# 15_2.net
KiCad netlist of a schematic drawn in EasyEDA Pro
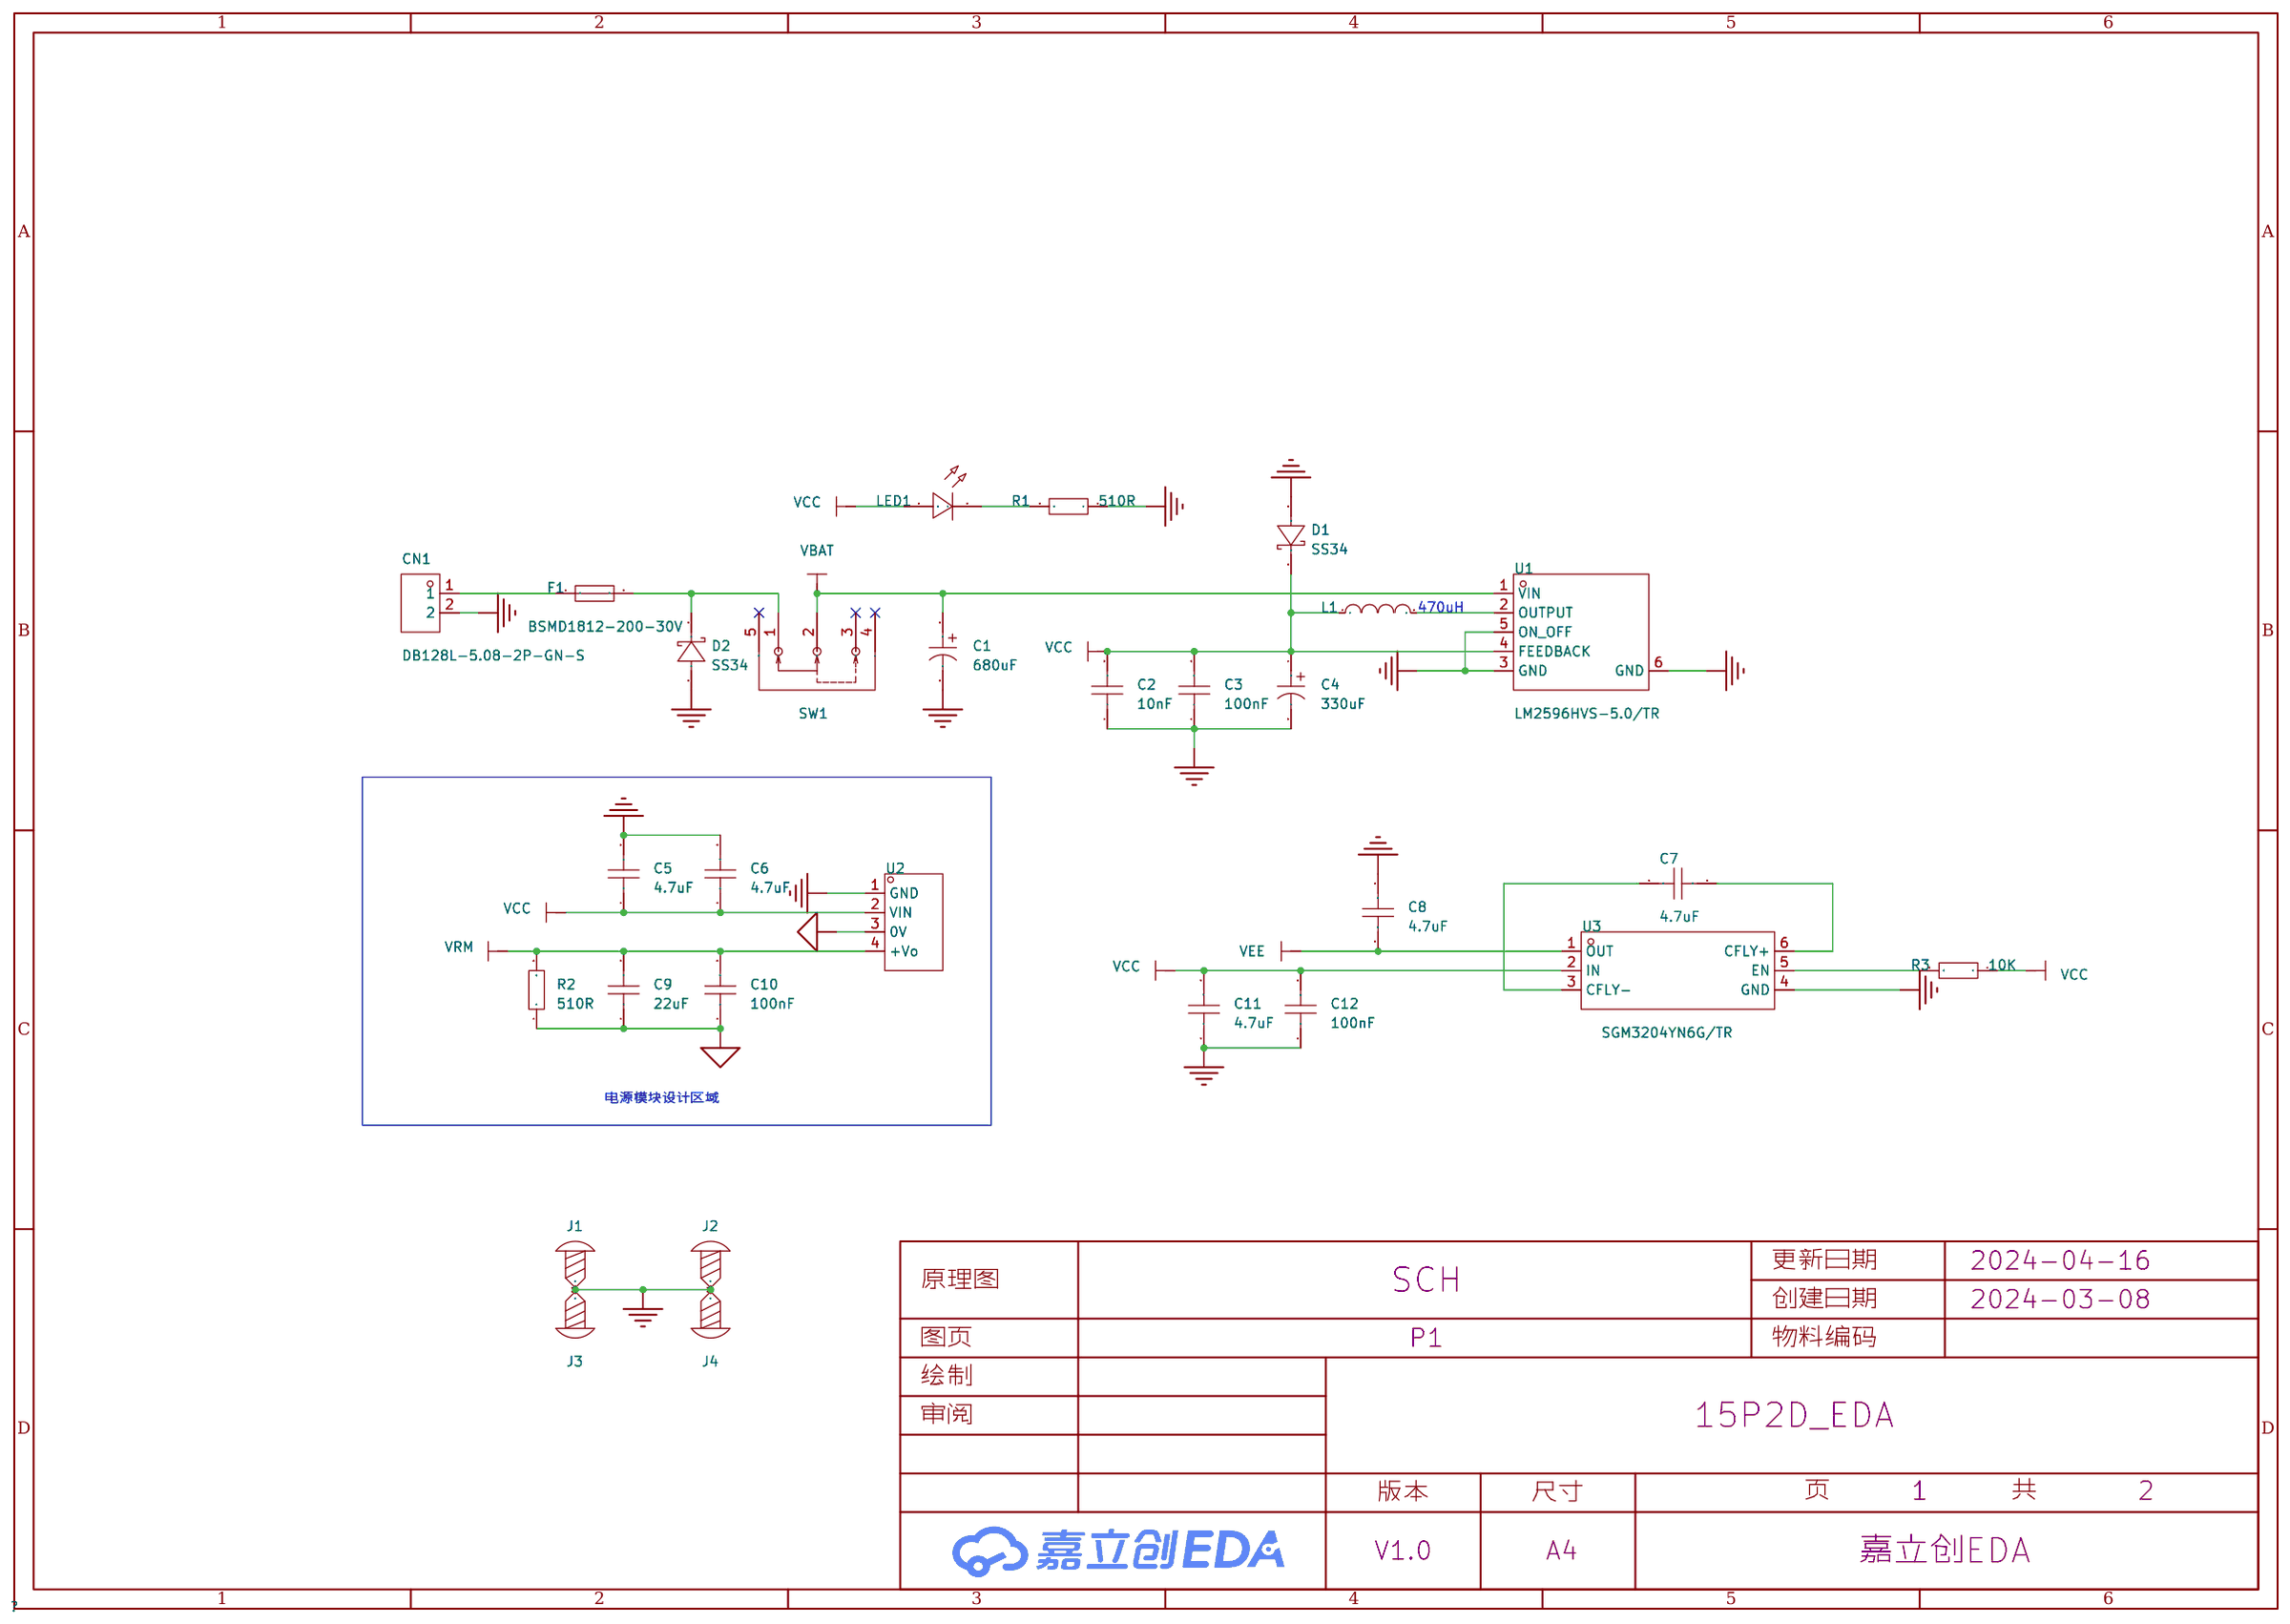
[diagram p0: P1]
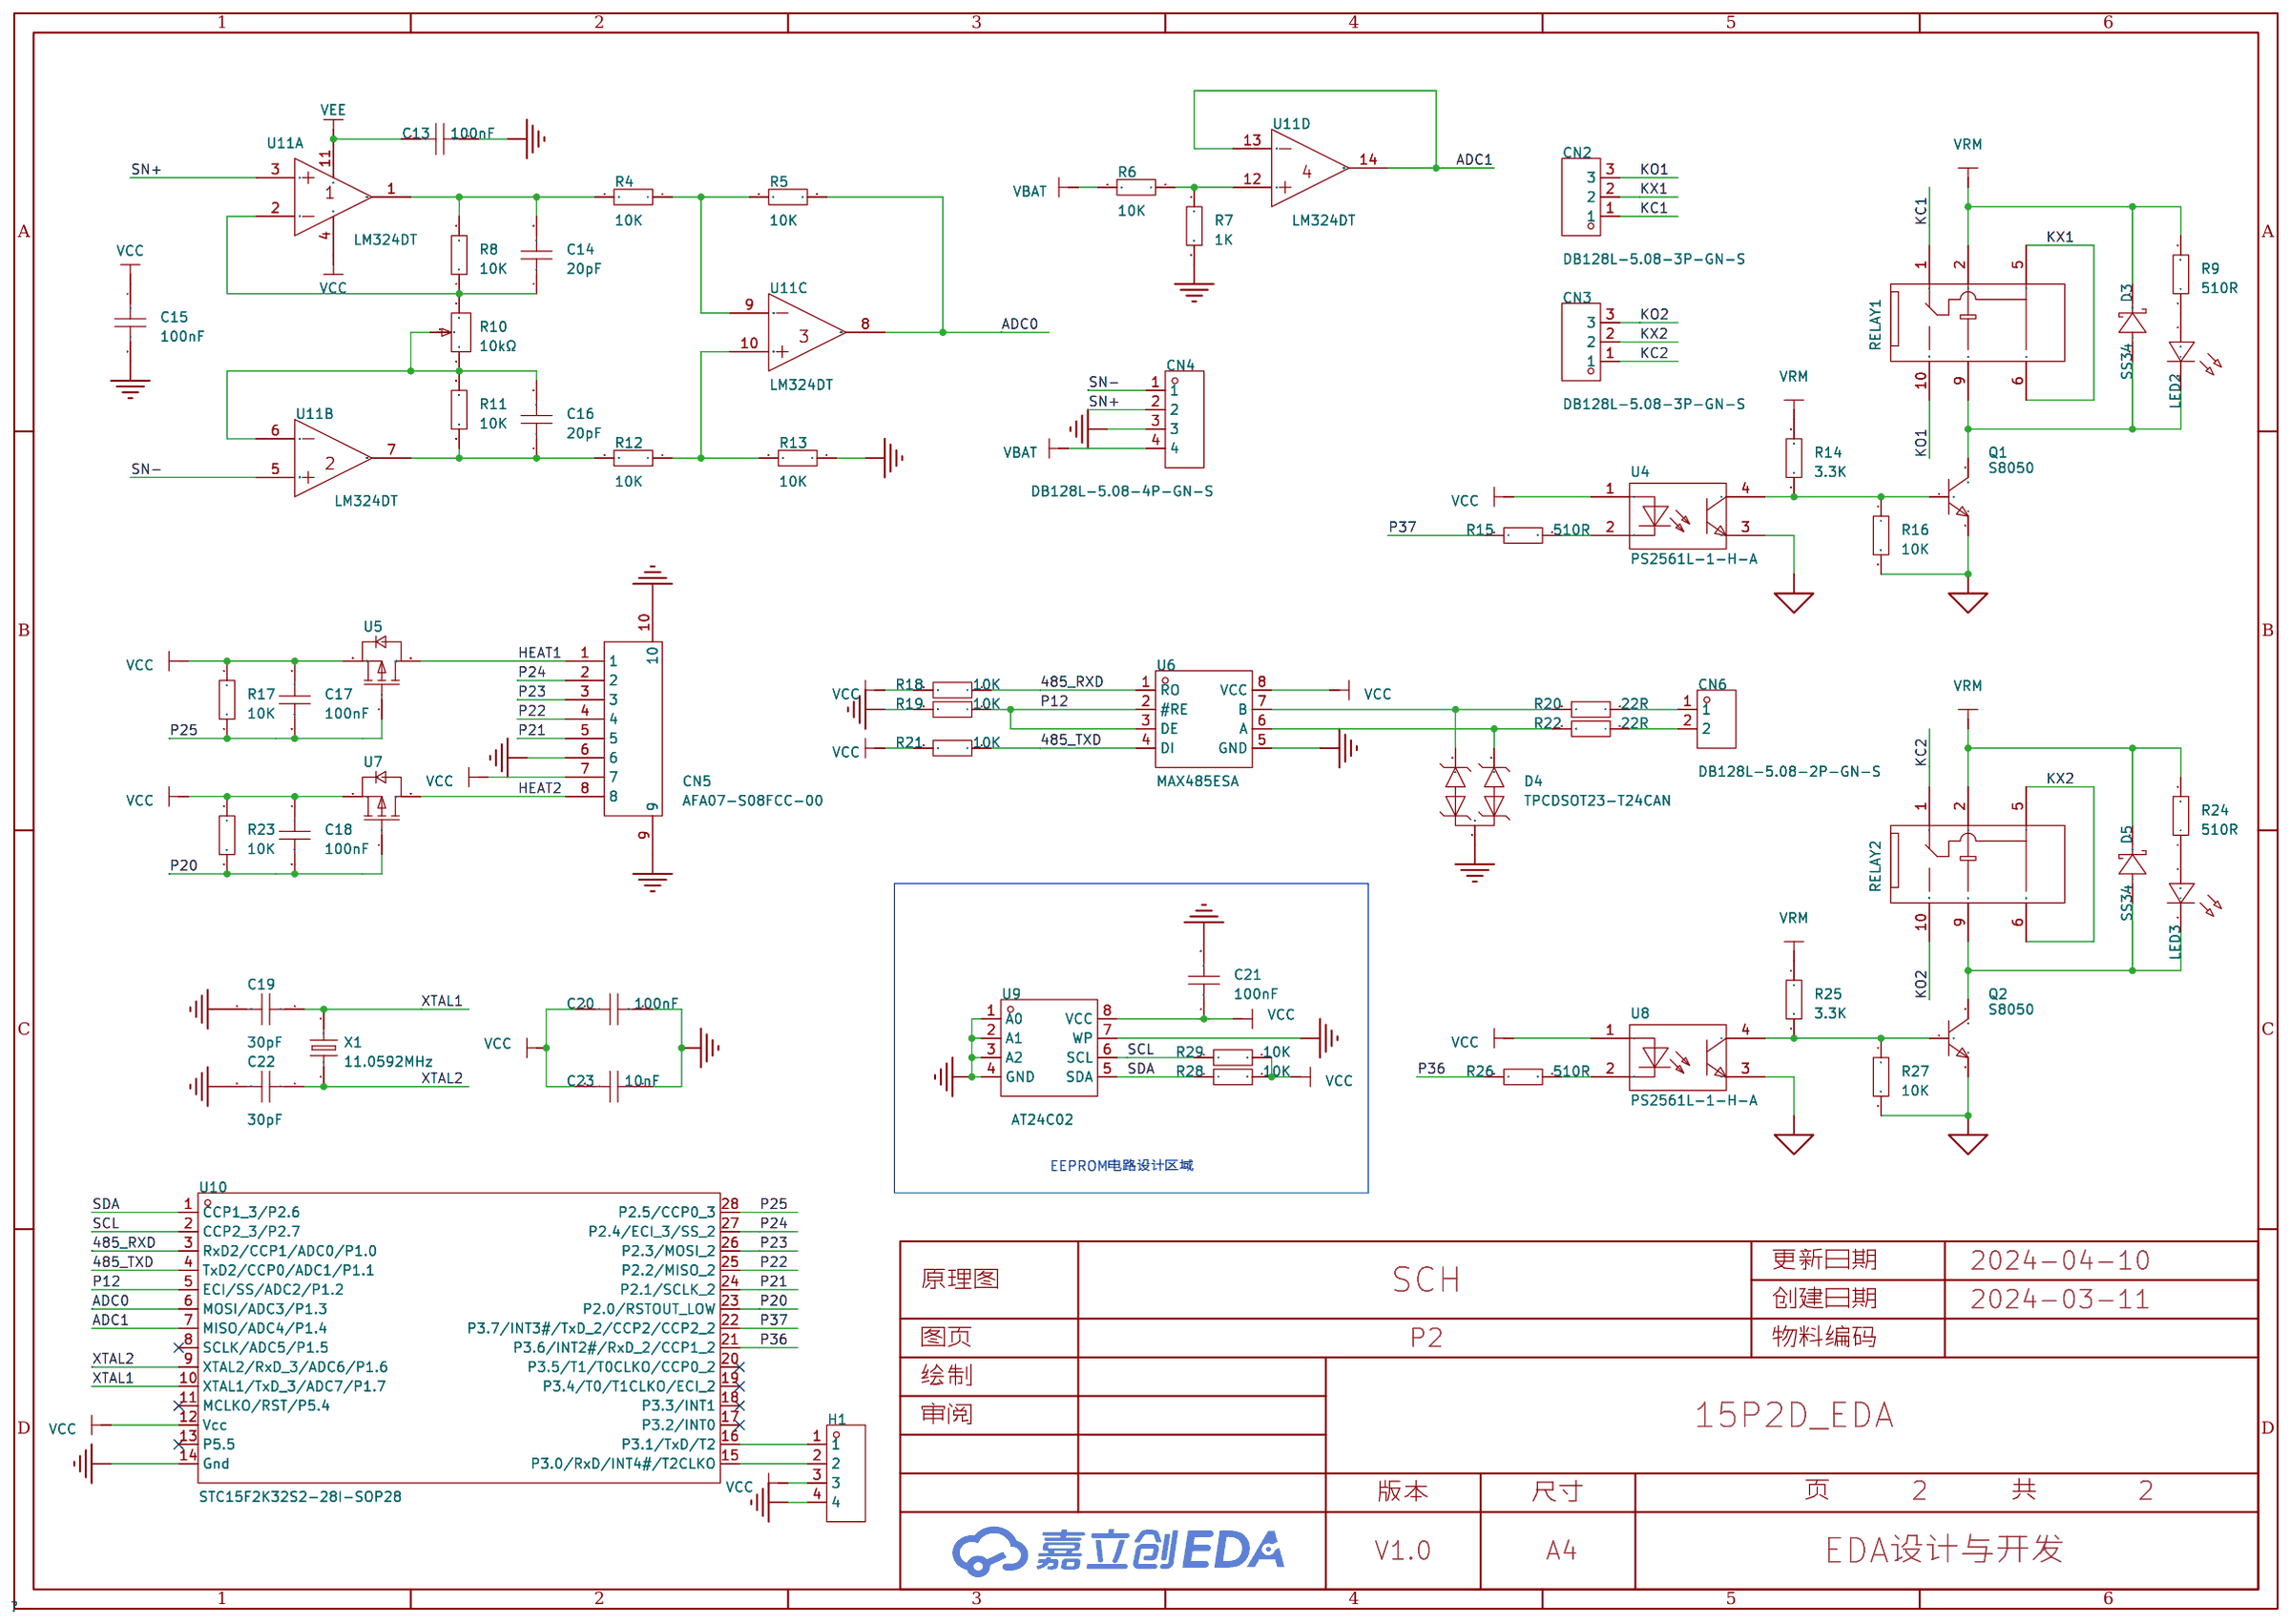
[diagram p1: P2]

(export (version "E")
  (design (tool "Eeschema 10.0.6"))
  (components
    (comp (ref "C1")
      (value "680uF")
      (footprint "easyedapro:CAP-SMD_BD10.0-L10.3-W10.3-LS11.3-FD")
      (description "容值:680uF;精度:±20%;额定电压:35V;纹波电流:380mA;")
      (fields (field (name "Manufacturer Part") "126RV0105") (field (name "Manufacturer") "KNSCHA(科尼盛)"))
      (libsource (lib "easyedapro") (part "126RV0105"))
    )
    (comp (ref "C2")
      (value "10nF")
      (footprint "easyedapro:C0805")
      (libsource (lib "easyedapro") (part "CapAcitance"))
    )
    (comp (ref "C3")
      (value "100nF")
      (footprint "easyedapro:C0805")
      (libsource (lib "easyedapro") (part "CapAcitance"))
    )
    (comp (ref "C4")
      (value "330uF")
      (footprint "easyedapro:CAP-SMD_BD6.3-L6.6-W6.6-LS7.6-RD")
      (description "容值:330uF;精度:±20%;额定电压:16V;纹波电流:170mA;")
      (fields (field (name "Manufacturer Part") "126RV0107") (field (name "Manufacturer") "KNSCHA(科尼盛)"))
      (libsource (lib "easyedapro") (part "126RV0107"))
    )
    (comp (ref "C5")
      (value "4.7uF")
      (footprint "easyedapro:C1206")
      (description "容值:22uF;精度:±10%;额定电压:16V;材质(温度系数):X5R;")
      (fields
        (field (name "Manufacturer Part") "CL31A226KOHNNNE")
        (field (name "Manufacturer") "SAMSUNG(三星)")
      )
      (libsource (lib "easyedapro") (part "CL31A226KOHNNNE"))
    )
    (comp (ref "C6")
      (value "4.7uF")
      (footprint "easyedapro:C1206")
      (description "容值:22uF;精度:±10%;额定电压:16V;材质(温度系数):X5R;")
      (fields
        (field (name "Manufacturer Part") "CL31A226KOHNNNE")
        (field (name "Manufacturer") "SAMSUNG(三星)")
      )
      (libsource (lib "easyedapro") (part "CL31A226KOHNNNE"))
    )
    (comp (ref "C7")
      (value "4.7uF")
      (footprint "easyedapro:C1206")
      (description "容值:22uF;精度:±10%;额定电压:16V;材质(温度系数):X5R;")
      (fields
        (field (name "Manufacturer Part") "CL31A226KOHNNNE")
        (field (name "Manufacturer") "SAMSUNG(三星)")
      )
      (libsource (lib "easyedapro") (part "CL31A226KOHNNNE"))
    )
    (comp (ref "C8")
      (value "4.7uF")
      (footprint "easyedapro:C1206")
      (description "容值:22uF;精度:±10%;额定电压:16V;材质(温度系数):X5R;")
      (fields
        (field (name "Manufacturer Part") "CL31A226KOHNNNE")
        (field (name "Manufacturer") "SAMSUNG(三星)")
      )
      (libsource (lib "easyedapro") (part "CL31A226KOHNNNE"))
    )
    (comp (ref "C9")
      (value "22uF")
      (footprint "easyedapro:C1206")
      (description "容值:22uF;精度:±10%;额定电压:16V;材质(温度系数):X5R;")
      (fields
        (field (name "Manufacturer Part") "CL31A226KOHNNNE")
        (field (name "Manufacturer") "SAMSUNG(三星)")
      )
      (libsource (lib "easyedapro") (part "CL31A226KOHNNNE"))
    )
    (comp (ref "C10")
      (value "100nF")
      (footprint "easyedapro:C0805")
      (libsource (lib "easyedapro") (part "CapAcitance"))
    )
    (comp (ref "C11")
      (value "4.7uF")
      (footprint "easyedapro:C1206")
      (description "容值:22uF;精度:±10%;额定电压:16V;材质(温度系数):X5R;")
      (fields
        (field (name "Manufacturer Part") "CL31A226KOHNNNE")
        (field (name "Manufacturer") "SAMSUNG(三星)")
      )
      (libsource (lib "easyedapro") (part "CL31A226KOHNNNE"))
    )
    (comp (ref "C12")
      (value "100nF")
      (footprint "easyedapro:C0805")
      (libsource (lib "easyedapro") (part "CapAcitance"))
    )
    (comp (ref "CN1")
      (value "DB128L-5.08-2P-GN-S")
      (footprint "easyedapro:CONN-TH_2P-P5.08_DB128L-5.08-2P")
      (fields (field (name "Manufacturer") "DORABO(地博电气)"))
      (libsource (lib "easyedapro") (part "DB128L-5.08-2P"))
    )
    (comp (ref "D1")
      (value "SS34")
      (footprint "easyedapro:SMA_L4.3-W2.5-LS5.0-RD")
      (description "二极管配置:独立式;正向压降(Vf):550mV@3A;直流反向耐压(Vr):40V;平均整流电流(Io):3A;")
      (fields (field (name "Manufacturer") "TWGMC(台湾迪嘉)"))
      (libsource (lib "easyedapro") (part "SS34_C727060"))
    )
    (comp (ref "D2")
      (value "SS34")
      (footprint "easyedapro:SMA_L4.3-W2.5-LS5.0-RD")
      (description "二极管配置:独立式;正向压降(Vf):550mV@3A;直流反向耐压(Vr):40V;平均整流电流(Io):3A;")
      (fields (field (name "Manufacturer") "TWGMC(台湾迪嘉)"))
      (libsource (lib "easyedapro") (part "SS34_C727060"))
    )
    (comp (ref "F1")
      (value "BSMD1812-200-30V")
      (footprint "easyedapro:F1812")
      (description "最大电压:30V;最大电流:40A;保持电流:2A;跳闸电流:4A;")
      (fields (field (name "Manufacturer") "BHFUSE(佰宏)"))
      (libsource (lib "easyedapro") (part "BSMD1812-200-30V"))
    )
    (comp (ref "J1") (value "~") (footprint "easyedapro:M2螺丝") (libsource (lib "easyedapro") (part "螺丝孔")))
    (comp (ref "J2") (value "~") (footprint "easyedapro:M2螺丝") (libsource (lib "easyedapro") (part "螺丝孔")))
    (comp (ref "J3") (value "~") (footprint "easyedapro:M2螺丝") (libsource (lib "easyedapro") (part "螺丝孔")))
    (comp (ref "J4") (value "~") (footprint "easyedapro:M2螺丝") (libsource (lib "easyedapro") (part "螺丝孔")))
    (comp (ref "L1")
      (value "470uH")
      (footprint "easyedapro:IND-SMD_L12.0-W12.0_YPRH120X")
      (description "电感值:470uH;精度:±20%;额定电流:1.06A;")
      (fields (field (name "Manufacturer Part") "YPRH1209-471M") (field (name "Manufacturer") "YJYCOIN(益嘉源)"))
      (libsource (lib "easyedapro") (part "YPRH1209-471M"))
    )
    (comp (ref "LED1")
      (value "~")
      (footprint "easyedapro:LED_TH-3mm")
      (libsource (lib "easyedapro") (part "LED_TH-R"))
    )
    (comp (ref "R1") (value "510R") (footprint "easyedapro:R0805") (libsource (lib "easyedapro") (part "电阻")))
    (comp (ref "R2") (value "510R") (footprint "easyedapro:R0805") (libsource (lib "easyedapro") (part "电阻")))
    (comp (ref "R3") (value "10K") (footprint "easyedapro:R0805") (libsource (lib "easyedapro") (part "电阻")))
    (comp (ref "SW1")
      (value "SK12D07VG4")
      (footprint "easyedapro:SW-TH_SK12D07VG4")
      (description "电路结构:单刀双掷;安装方式:侧插;额定电流(DC):500mA;额定电压(DC):50V;额定电流(AC):-;额定电压(AC):-;机械寿命:5千次;")
      (fields (field (name "Manufacturer") "SHOU HAN(首韩)"))
      (libsource (lib "easyedapro") (part "SK12D07VG4"))
    )
    (comp (ref "U1")
      (value "LM2596HVS-5.0/TR")
      (footprint "easyedapro:TO-263-5_L10.2-W8.9-P1.70-LS15.2-BR")
      (fields (field (name "Manufacturer") "HGSEMI(华冠)"))
      (libsource (lib "easyedapro") (part "LM2596HVS-5.0/TR"))
    )
    (comp (ref "U2") (value "~") (libsource (lib "easyedapro") (part "PCON")))
    (comp (ref "U3")
      (value "SGM3204YN6G/TR")
      (footprint "easyedapro:SOT-23-6_L2.9-W1.6-P0.95-LS2.8-BR")
      (description "功能类型:-;输入电压:1.4V~5.5V;输出电压:-5.5V~-1.4V;输出电流(最大值):200mA;")
      (fields (field (name "Manufacturer") "SGMICRO(圣邦微)"))
      (libsource (lib "easyedapro") (part "SGM3204YN6G/TR"))
    )
    (comp (ref "C13")
      (value "100nF")
      (footprint "easyedapro:C0805")
      (libsource (lib "easyedapro") (part "CapAcitance"))
    )
    (comp (ref "C14")
      (value "20pF")
      (footprint "easyedapro:C0805")
      (libsource (lib "easyedapro") (part "CapAcitance"))
    )
    (comp (ref "C15")
      (value "100nF")
      (footprint "easyedapro:C0805")
      (libsource (lib "easyedapro") (part "CapAcitance"))
    )
    (comp (ref "C16")
      (value "20pF")
      (footprint "easyedapro:C0805")
      (libsource (lib "easyedapro") (part "CapAcitance"))
    )
    (comp (ref "C17")
      (value "100nF")
      (footprint "easyedapro:C0805")
      (libsource (lib "easyedapro") (part "CapAcitance"))
    )
    (comp (ref "C18")
      (value "100nF")
      (footprint "easyedapro:C0805")
      (libsource (lib "easyedapro") (part "CapAcitance"))
    )
    (comp (ref "C19")
      (value "30pF")
      (footprint "easyedapro:C0805")
      (libsource (lib "easyedapro") (part "CapAcitance"))
    )
    (comp (ref "C20")
      (value "100nF")
      (footprint "easyedapro:C0805")
      (libsource (lib "easyedapro") (part "CapAcitance"))
    )
    (comp (ref "C21")
      (value "100nF")
      (footprint "easyedapro:C0805")
      (libsource (lib "easyedapro") (part "CapAcitance"))
    )
    (comp (ref "C22")
      (value "30pF")
      (footprint "easyedapro:C0805")
      (libsource (lib "easyedapro") (part "CapAcitance"))
    )
    (comp (ref "C23")
      (value "10nF")
      (footprint "easyedapro:C0805")
      (libsource (lib "easyedapro") (part "CapAcitance"))
    )
    (comp (ref "CN2")
      (value "DB128L-5.08-3P-GN-S")
      (footprint "easyedapro:CONN-TH_DB128L-5.08-3P")
      (fields (field (name "Manufacturer") "DORABO(地博电气)"))
      (libsource (lib "easyedapro") (part "DB128L-5.08-3P"))
    )
    (comp (ref "CN3")
      (value "DB128L-5.08-3P-GN-S")
      (footprint "easyedapro:CONN-TH_DB128L-5.08-3P")
      (fields (field (name "Manufacturer") "DORABO(地博电气)"))
      (libsource (lib "easyedapro") (part "DB128L-5.08-3P"))
    )
    (comp (ref "CN4")
      (value "DB128L-5.08-4P-GN-S")
      (footprint "easyedapro:CONN-TH_4P_DB128L-5.08-4P-GN-S")
      (fields (field (name "Manufacturer") "DORABO(地博电气)"))
      (libsource (lib "easyedapro") (part "DB128L-5.08-4P-GN-S"))
    )
    (comp (ref "CN5")
      (value "AFA07-S08FCC-00")
      (footprint "easyedapro:FPC-SMD_P1.00-8P_LCS-XJ-H2.5")
      (description "锁定特性:抽屉式;触点类型:下接;触点数量:8P;间距:1mm;安装类型:卧贴;")
      (fields (field (name "Manufacturer") "JS(钜硕电子)"))
      (libsource (lib "easyedapro") (part "AFA07-S08FCC-00"))
    )
    (comp (ref "CN6")
      (value "DB128L-5.08-2P-GN-S")
      (footprint "easyedapro:CONN-TH_2P-P5.08_DB128L-5.08-2P")
      (fields (field (name "Manufacturer") "DORABO(地博电气)"))
      (libsource (lib "easyedapro") (part "DB128L-5.08-2P"))
    )
    (comp (ref "D3")
      (value "SS34")
      (footprint "easyedapro:SMA_L4.3-W2.5-LS5.0-RD")
      (description "二极管配置:独立式;正向压降(Vf):550mV@3A;直流反向耐压(Vr):40V;平均整流电流(Io):3A;")
      (fields (field (name "Manufacturer") "TWGMC(台湾迪嘉)"))
      (libsource (lib "easyedapro") (part "SS34_C727060"))
    )
    (comp (ref "D4")
      (value "TPCDSOT23-T24CAN")
      (footprint "easyedapro:SOT-23-3_L2.9-W1.3-P1.90-LS2.4-BR")
      (fields (field (name "Manufacturer") "TECH PUBLIC(台舟)"))
      (libsource (lib "easyedapro") (part "TPCDSOT23-T24CAN"))
    )
    (comp (ref "D5")
      (value "SS34")
      (footprint "easyedapro:SMA_L4.3-W2.5-LS5.0-RD")
      (description "二极管配置:独立式;正向压降(Vf):550mV@3A;直流反向耐压(Vr):40V;平均整流电流(Io):3A;")
      (fields (field (name "Manufacturer") "TWGMC(台湾迪嘉)"))
      (libsource (lib "easyedapro") (part "SS34_C727060"))
    )
    (comp (ref "H1")
      (value "~")
      (footprint "easyedapro:HDR-TH_4P-P2.54-V-F")
      (libsource (lib "easyedapro") (part "2.54-1*4P母"))
    )
    (comp (ref "LED2")
      (value "~")
      (footprint "easyedapro:LED_TH-3mm")
      (libsource (lib "easyedapro") (part "LED_TH-G"))
    )
    (comp (ref "LED3")
      (value "~")
      (footprint "easyedapro:LED_TH-3mm")
      (libsource (lib "easyedapro") (part "LED_TH-G"))
    )
    (comp (ref "Q1")
      (value "S8050")
      (footprint "easyedapro:SOT-23-3_L2.9-W1.3-P1.90-LS2.4-BR")
      (description "晶体管类型:NPN;集电极电流(Ic):500mA;集射极击穿电压(Vceo):25V;功率(Pd):300mW;")
      (fields (field (name "Manufacturer") "YONGYUTAI(永裕泰)"))
      (libsource (lib "easyedapro") (part "S8050_C2891804"))
    )
    (comp (ref "Q2")
      (value "S8050")
      (footprint "easyedapro:SOT-23-3_L2.9-W1.3-P1.90-LS2.4-BR")
      (description "晶体管类型:NPN;集电极电流(Ic):500mA;集射极击穿电压(Vceo):25V;功率(Pd):300mW;")
      (fields (field (name "Manufacturer") "YONGYUTAI(永裕泰)"))
      (libsource (lib "easyedapro") (part "S8050_C2891804"))
    )
    (comp (ref "R4") (value "10K") (footprint "easyedapro:R0805") (libsource (lib "easyedapro") (part "电阻")))
    (comp (ref "R5") (value "10K") (footprint "easyedapro:R0805") (libsource (lib "easyedapro") (part "电阻")))
    (comp (ref "R6") (value "10K") (footprint "easyedapro:R0805") (libsource (lib "easyedapro") (part "电阻")))
    (comp (ref "R7") (value "1K") (footprint "easyedapro:R0805") (libsource (lib "easyedapro") (part "电阻")))
    (comp (ref "R8") (value "10K") (footprint "easyedapro:R0805") (libsource (lib "easyedapro") (part "电阻")))
    (comp (ref "R9") (value "510R") (footprint "easyedapro:R0805") (libsource (lib "easyedapro") (part "电阻")))
    (comp (ref "R10")
      (value "10kΩ")
      (footprint "easyedapro:RES-ADJ-TH_3P-L10.0-W10.0-P2.50-BL-BS")
      (description "阻值:20kΩ;精度:±10%;功率:500mW;温度系数:±100ppm/°C;")
      (fields (field (name "Manufacturer Part") "3296W-1-203LF") (field (name "Manufacturer") "BOURNS"))
      (libsource (lib "easyedapro") (part "3296W-1-203LF"))
    )
    (comp (ref "R11") (value "10K") (footprint "easyedapro:R0805") (libsource (lib "easyedapro") (part "电阻")))
    (comp (ref "R12") (value "10K") (footprint "easyedapro:R0805") (libsource (lib "easyedapro") (part "电阻")))
    (comp (ref "R13") (value "10K") (footprint "easyedapro:R0805") (libsource (lib "easyedapro") (part "电阻")))
    (comp (ref "R14")
      (value "3.3K")
      (footprint "easyedapro:R0805")
      (libsource (lib "easyedapro") (part "电阻"))
    )
    (comp (ref "R15")
      (value "510R")
      (footprint "easyedapro:R0805")
      (libsource (lib "easyedapro") (part "电阻"))
    )
    (comp (ref "R16") (value "10K") (footprint "easyedapro:R0805") (libsource (lib "easyedapro") (part "电阻")))
    (comp (ref "R17") (value "10K") (footprint "easyedapro:R0805") (libsource (lib "easyedapro") (part "电阻")))
    (comp (ref "R18") (value "10K") (footprint "easyedapro:R0805") (libsource (lib "easyedapro") (part "电阻")))
    (comp (ref "R19") (value "10K") (footprint "easyedapro:R0805") (libsource (lib "easyedapro") (part "电阻")))
    (comp (ref "R20") (value "22R") (footprint "easyedapro:R0805") (libsource (lib "easyedapro") (part "电阻")))
    (comp (ref "R21") (value "10K") (footprint "easyedapro:R0805") (libsource (lib "easyedapro") (part "电阻")))
    (comp (ref "R22") (value "22R") (footprint "easyedapro:R0805") (libsource (lib "easyedapro") (part "电阻")))
    (comp (ref "R23") (value "10K") (footprint "easyedapro:R0805") (libsource (lib "easyedapro") (part "电阻")))
    (comp (ref "R24")
      (value "510R")
      (footprint "easyedapro:R0805")
      (libsource (lib "easyedapro") (part "电阻"))
    )
    (comp (ref "R25")
      (value "3.3K")
      (footprint "easyedapro:R0805")
      (libsource (lib "easyedapro") (part "电阻"))
    )
    (comp (ref "R26")
      (value "510R")
      (footprint "easyedapro:R0805")
      (libsource (lib "easyedapro") (part "电阻"))
    )
    (comp (ref "R27") (value "10K") (footprint "easyedapro:R0805") (libsource (lib "easyedapro") (part "电阻")))
    (comp (ref "R28") (value "10K") (footprint "easyedapro:R0805") (libsource (lib "easyedapro") (part "电阻")))
    (comp (ref "R29") (value "10K") (footprint "easyedapro:R0805") (libsource (lib "easyedapro") (part "电阻")))
    (comp (ref "RELAY1")
      (value "G5V-1 DC5")
      (footprint "easyedapro:RELAY-TH_G5V-1")
      (description "线圈电压:5V;触点形式:一组转换:1C(单刀双掷-转换);触点容量(电阻负载):-;最大切换电压:125V@AC；60V@DC;最大切换电流:1A;")
      (fields (field (name "Manufacturer") "OMRON(欧姆龙)"))
      (libsource (lib "easyedapro") (part "G5V-1-5VDC"))
    )
    (comp (ref "RELAY2")
      (value "G5V-1 DC5")
      (footprint "easyedapro:RELAY-TH_G5V-1")
      (description "线圈电压:5V;触点形式:一组转换:1C(单刀双掷-转换);触点容量(电阻负载):-;最大切换电压:125V@AC；60V@DC;最大切换电流:1A;")
      (fields (field (name "Manufacturer") "OMRON(欧姆龙)"))
      (libsource (lib "easyedapro") (part "G5V-1-5VDC"))
    )
    (comp (ref "U4")
      (value "PS2561L-1-H-A")
      (footprint "easyedapro:SOP-4_L6.5-W4.6-P2.54-LS9.6-TL")
      (fields (field (name "Manufacturer") "California Eastern Laboratories"))
      (libsource (lib "easyedapro") (part "PS2561L-1-H-A"))
    )
    (comp (ref "U5")
      (value "SI2301-ZE")
      (footprint "easyedapro:SOT-23-3_L2.9-W1.3-P1.90-LS2.4-BR")
      (fields (field (name "Manufacturer") "HXY MOSFET(华轩阳电子)"))
      (libsource (lib "easyedapro") (part "SI2301-ZE"))
    )
    (comp (ref "U6")
      (value "MAX485ESA")
      (footprint "easyedapro:SOP-8_L5.0-W4.0-P1.27-LS6.0-BL")
      (fields (field (name "Manufacturer") "UMW(友台半导体)"))
      (libsource (lib "easyedapro") (part "MAX485EAS"))
    )
    (comp (ref "U7")
      (value "SI2301-ZE")
      (footprint "easyedapro:SOT-23-3_L2.9-W1.3-P1.90-LS2.4-BR")
      (fields (field (name "Manufacturer") "HXY MOSFET(华轩阳电子)"))
      (libsource (lib "easyedapro") (part "SI2301-ZE"))
    )
    (comp (ref "U8")
      (value "PS2561L-1-H-A")
      (footprint "easyedapro:SOP-4_L6.5-W4.6-P2.54-LS9.6-TL")
      (fields (field (name "Manufacturer") "California Eastern Laboratories"))
      (libsource (lib "easyedapro") (part "PS2561L-1-H-A"))
    )
    (comp (ref "U9")
      (value "AT24C02")
      (footprint "easyedapro:SOP-8_L4.9-W3.9-P1.27-LS6.0-BL")
      (description "接口类型:I2C;存储容量:2Kbit;时钟频率(fc):400kHz~1MHz;")
      (fields (field (name "Manufacturer") "HXY MOSFET(华轩阳电子)"))
      (libsource (lib "easyedapro") (part "AT24C02_C7470930"))
    )
    (comp (ref "U10")
      (value "STC15F2K32S2-28I-SOP28")
      (footprint "easyedapro:SOP-28_L17.9-W7.5-P1.27-LS10.3-BL")
      (fields (field (name "Manufacturer") "STC(宏晶)"))
      (libsource (lib "easyedapro") (part "STC15F2K32S2-28I-SOP28"))
    )
    (comp (ref "U11")
      (value "LM324DT")
      (footprint "easyedapro:SOIC-14_L8.7-W3.9-P1.27-LS6.0-BL")
      (description "放大器数:四路;增益带宽积(GBP):1.3MHz;输入偏置电流(Ib):20nA;压摆率(SR):0.4V/us;带宽(-3db):-;")
      (fields (field (name "Manufacturer") "ST(意法半导体)"))
      (libsource (lib "easyedapro") (part "LM324DT"))
    )
    (comp (ref "X1")
      (value "11.0592MHz")
      (footprint "easyedapro:HC-49US_L11.5-W4.5-P4.88")
      (description "晶振类型:直插晶振;频率:11.0592MHz;常温频差:±30ppm;外接负载电容:20pF;频率稳定度(全温):±30ppm;")
      (fields
        (field (name "Manufacturer Part") "TAXD11.0592M2GLFBET2T")
        (field (name "Manufacturer") "YJX(雅晶鑫)")
      )
      (libsource (lib "easyedapro") (part "HC-49S11.0592MHZ20PF30PPM"))
    )
  )
  (nets
    (net (code "1") (name "0") (class "Default")
      (node (ref "C10") (pin "1") (pinfunction "1_1") (pintype "input"))
      (node (ref "C9") (pin "1") (pinfunction "1_1") (pintype "unspecified"))
      (node (ref "Q1") (pin "2") (pinfunction "E_2") (pintype "unspecified"))
      (node (ref "Q2") (pin "2") (pinfunction "E_2") (pintype "unspecified"))
      (node (ref "R16") (pin "2") (pinfunction "2_2") (pintype "input"))
      (node (ref "R2") (pin "1") (pinfunction "1_1") (pintype "input"))
      (node (ref "R27") (pin "2") (pinfunction "2_2") (pintype "input"))
      (node (ref "U2") (pin "3") (pinfunction "0V_3") (pintype "input"))
      (node (ref "U4") (pin "3") (pinfunction "3_3") (pintype "input"))
      (node (ref "U8") (pin "3") (pinfunction "3_3") (pintype "input"))
    )
    (net (code "2") (name "485_RXD") (class "Default")
      (node (ref "R18") (pin "1") (pinfunction "1_1") (pintype "input"))
      (node (ref "U10") (pin "3") (pinfunction "RxD2/CCP1/ADC0/P1.0_3") (pintype "input"))
      (node (ref "U6") (pin "1") (pinfunction "RO_1") (pintype "unspecified"))
    )
    (net (code "3") (name "485_TXD") (class "Default")
      (node (ref "R21") (pin "1") (pinfunction "1_1") (pintype "input"))
      (node (ref "U10") (pin "4") (pinfunction "TxD2/CCP0/ADC1/P1.1_4") (pintype "input"))
      (node (ref "U6") (pin "4") (pinfunction "DI_4") (pintype "unspecified"))
    )
    (net (code "4") (name "ADC0") (class "Default")
      (node (ref "R5") (pin "1") (pinfunction "1_1") (pintype "input"))
      (node (ref "U10") (pin "6") (pinfunction "MOSI/ADC3/P1.3_6") (pintype "input"))
      (node (ref "U11") (pin "8") (pinfunction "OUT3_8") (pintype "unspecified"))
    )
    (net (code "5") (name "ADC1") (class "Default")
      (node (ref "U10") (pin "7") (pinfunction "MISO/ADC4/P1.4_7") (pintype "input"))
      (node (ref "U11") (pin "13") (pinfunction "IN4-_13") (pintype "unspecified"))
      (node (ref "U11") (pin "14") (pinfunction "OUT4_14") (pintype "unspecified"))
    )
    (net (code "6") (name "GND") (class "Default")
      (node (ref "C1") (pin "2") (pinfunction "2_2") (pintype "input"))
      (node (ref "C11") (pin "1") (pinfunction "1_1") (pintype "unspecified"))
      (node (ref "C12") (pin "1") (pinfunction "1_1") (pintype "input"))
      (node (ref "C13") (pin "1") (pinfunction "1_1") (pintype "input"))
      (node (ref "C15") (pin "2") (pinfunction "2_2") (pintype "input"))
      (node (ref "C19") (pin "2") (pinfunction "2_2") (pintype "input"))
      (node (ref "C2") (pin "1") (pinfunction "1_1") (pintype "input"))
      (node (ref "C20") (pin "1") (pinfunction "1_1") (pintype "input"))
      (node (ref "C21") (pin "2") (pinfunction "2_2") (pintype "input"))
      (node (ref "C22") (pin "2") (pinfunction "2_2") (pintype "input"))
      (node (ref "C23") (pin "1") (pinfunction "1_1") (pintype "input"))
      (node (ref "C3") (pin "1") (pinfunction "1_1") (pintype "input"))
      (node (ref "C4") (pin "2") (pinfunction "2_2") (pintype "input"))
      (node (ref "C5") (pin "2") (pinfunction "2_2") (pintype "unspecified"))
      (node (ref "C6") (pin "2") (pinfunction "2_2") (pintype "unspecified"))
      (node (ref "C8") (pin "1") (pinfunction "1_1") (pintype "unspecified"))
      (node (ref "CN1") (pin "2") (pinfunction "2_2") (pintype "unspecified"))
      (node (ref "CN4") (pin "3") (pinfunction "3_3") (pintype "unspecified"))
      (node (ref "CN5") (pin "10") (pinfunction "10_10") (pintype "unspecified"))
      (node (ref "CN5") (pin "6") (pinfunction "6_6") (pintype "unspecified"))
      (node (ref "CN5") (pin "9") (pinfunction "9_9") (pintype "unspecified"))
      (node (ref "D1") (pin "2") (pinfunction "A_2") (pintype "unspecified"))
      (node (ref "D2") (pin "2") (pinfunction "A_2") (pintype "unspecified"))
      (node (ref "D4") (pin "3") (pinfunction "3_3") (pintype "unspecified"))
      (node (ref "H1") (pin "4") (pinfunction "4_4") (pintype "unspecified"))
      (node (ref "J1") (pin "1") (pinfunction "1_1") (pintype "input"))
      (node (ref "J2") (pin "1") (pinfunction "1_1") (pintype "input"))
      (node (ref "J3") (pin "1") (pinfunction "1_1") (pintype "input"))
      (node (ref "J4") (pin "1") (pinfunction "1_1") (pintype "input"))
      (node (ref "R1") (pin "1") (pinfunction "1_1") (pintype "input"))
      (node (ref "R13") (pin "1") (pinfunction "1_1") (pintype "input"))
      (node (ref "R19") (pin "2") (pinfunction "2_2") (pintype "input"))
      (node (ref "R7") (pin "2") (pinfunction "2_2") (pintype "input"))
      (node (ref "U1") (pin "3") (pinfunction "GND_3") (pintype "input"))
      (node (ref "U1") (pin "5") (pinfunction "ON_OFF_5") (pintype "input"))
      (node (ref "U1") (pin "6") (pinfunction "GND_6") (pintype "input"))
      (node (ref "U10") (pin "14") (pinfunction "Gnd_14") (pintype "input"))
      (node (ref "U2") (pin "1") (pinfunction "GND_1") (pintype "input"))
      (node (ref "U3") (pin "4") (pinfunction "GND_4") (pintype "unspecified"))
      (node (ref "U6") (pin "5") (pinfunction "GND_5") (pintype "unspecified"))
      (node (ref "U9") (pin "1") (pinfunction "A0_1") (pintype "unspecified"))
      (node (ref "U9") (pin "2") (pinfunction "A1_2") (pintype "unspecified"))
      (node (ref "U9") (pin "3") (pinfunction "A2_3") (pintype "unspecified"))
      (node (ref "U9") (pin "4") (pinfunction "GND_4") (pintype "unspecified"))
      (node (ref "U9") (pin "7") (pinfunction "WP_7") (pintype "unspecified"))
    )
    (net (code "7") (name "HEAT1") (class "Default")
      (node (ref "CN5") (pin "1") (pinfunction "1_1") (pintype "unspecified"))
      (node (ref "U5") (pin "3") (pinfunction "D_3") (pintype "unspecified"))
    )
    (net (code "8") (name "HEAT2") (class "Default")
      (node (ref "CN5") (pin "8") (pinfunction "8_8") (pintype "unspecified"))
      (node (ref "U7") (pin "3") (pinfunction "D_3") (pintype "unspecified"))
    )
    (net (code "9") (name "KC1") (class "Default")
      (node (ref "CN2") (pin "1") (pinfunction "1_1") (pintype "unspecified"))
      (node (ref "RELAY1") (pin "1") (pinfunction "1_1") (pintype "input"))
    )
    (net (code "10") (name "KC2") (class "Default")
      (node (ref "CN3") (pin "1") (pinfunction "1_1") (pintype "unspecified"))
      (node (ref "RELAY2") (pin "1") (pinfunction "1_1") (pintype "input"))
    )
    (net (code "11") (name "KO1") (class "Default")
      (node (ref "CN2") (pin "3") (pinfunction "3_3") (pintype "unspecified"))
      (node (ref "RELAY1") (pin "10") (pinfunction "10_10") (pintype "input"))
    )
    (net (code "12") (name "KO2") (class "Default")
      (node (ref "CN3") (pin "3") (pinfunction "3_3") (pintype "unspecified"))
      (node (ref "RELAY2") (pin "10") (pinfunction "10_10") (pintype "input"))
    )
    (net (code "13") (name "KX1") (class "Default")
      (node (ref "CN2") (pin "2") (pinfunction "2_2") (pintype "unspecified"))
      (node (ref "RELAY1") (pin "5") (pinfunction "5_5") (pintype "input"))
      (node (ref "RELAY1") (pin "6") (pinfunction "6_6") (pintype "input"))
    )
    (net (code "14") (name "KX2") (class "Default")
      (node (ref "CN3") (pin "2") (pinfunction "2_2") (pintype "unspecified"))
      (node (ref "RELAY2") (pin "5") (pinfunction "5_5") (pintype "input"))
      (node (ref "RELAY2") (pin "6") (pinfunction "6_6") (pintype "input"))
    )
    (net (code "15") (name "Net-(CN1-Pad1)") (class "Default")
      (node (ref "CN1") (pin "1") (pinfunction "1_1") (pintype "unspecified"))
      (node (ref "F1") (pin "1") (pinfunction "1_1") (pintype "unspecified"))
    )
    (net (code "16") (name "Net-(CN6-Pad1)") (class "Default")
      (node (ref "CN6") (pin "1") (pinfunction "1_1") (pintype "unspecified"))
      (node (ref "R20") (pin "1") (pinfunction "1_1") (pintype "input"))
    )
    (net (code "17") (name "Net-(CN6-Pad2)") (class "Default")
      (node (ref "CN6") (pin "2") (pinfunction "2_2") (pintype "unspecified"))
      (node (ref "R22") (pin "1") (pinfunction "1_1") (pintype "input"))
    )
    (net (code "18") (name "Net-(D2-C)") (class "Default")
      (node (ref "D2") (pin "1") (pinfunction "C_1") (pintype "unspecified"))
      (node (ref "F1") (pin "2") (pinfunction "2_2") (pintype "unspecified"))
      (node (ref "SW1") (pin "1") (pinfunction "1_1") (pintype "unspecified"))
    )
    (net (code "19") (name "Net-(D3-A)") (class "Default")
      (node (ref "D3") (pin "2") (pinfunction "A_2") (pintype "unspecified"))
      (node (ref "LED2") (pin "2") (pinfunction "A_2") (pintype "input"))
      (node (ref "Q1") (pin "3") (pinfunction "C_3") (pintype "unspecified"))
      (node (ref "RELAY1") (pin "9") (pinfunction "9_9") (pintype "input"))
    )
    (net (code "20") (name "Net-(D5-A)") (class "Default")
      (node (ref "D5") (pin "2") (pinfunction "A_2") (pintype "unspecified"))
      (node (ref "LED3") (pin "2") (pinfunction "A_2") (pintype "input"))
      (node (ref "Q2") (pin "3") (pinfunction "C_3") (pintype "unspecified"))
      (node (ref "RELAY2") (pin "9") (pinfunction "9_9") (pintype "input"))
    )
    (net (code "21") (name "Net-(LED1-A)") (class "Default")
      (node (ref "LED1") (pin "2") (pinfunction "A_2") (pintype "input"))
      (node (ref "R1") (pin "2") (pinfunction "2_2") (pintype "input"))
    )
    (net (code "22") (name "Net-(LED2-C)") (class "Default")
      (node (ref "LED2") (pin "1") (pinfunction "C_1") (pintype "input"))
      (node (ref "R9") (pin "1") (pinfunction "1_1") (pintype "input"))
    )
    (net (code "23") (name "Net-(LED3-C)") (class "Default")
      (node (ref "LED3") (pin "1") (pinfunction "C_1") (pintype "input"))
      (node (ref "R24") (pin "1") (pinfunction "1_1") (pintype "input"))
    )
    (net (code "24") (name "Net-(Q1-B)") (class "Default")
      (node (ref "Q1") (pin "1") (pinfunction "B_1") (pintype "unspecified"))
      (node (ref "R14") (pin "2") (pinfunction "2_2") (pintype "input"))
      (node (ref "R16") (pin "1") (pinfunction "1_1") (pintype "input"))
      (node (ref "U4") (pin "4") (pinfunction "4_4") (pintype "input"))
    )
    (net (code "25") (name "Net-(Q2-B)") (class "Default")
      (node (ref "Q2") (pin "1") (pinfunction "B_1") (pintype "unspecified"))
      (node (ref "R25") (pin "2") (pinfunction "2_2") (pintype "input"))
      (node (ref "R27") (pin "1") (pinfunction "1_1") (pintype "input"))
      (node (ref "U8") (pin "4") (pinfunction "4_4") (pintype "input"))
    )
    (net (code "26") (name "Net-(R15-Pad2)") (class "Default")
      (node (ref "R15") (pin "2") (pinfunction "2_2") (pintype "input"))
      (node (ref "U4") (pin "2") (pinfunction "2_2") (pintype "input"))
    )
    (net (code "27") (name "Net-(R26-Pad2)") (class "Default")
      (node (ref "R26") (pin "2") (pinfunction "2_2") (pintype "input"))
      (node (ref "U8") (pin "2") (pinfunction "2_2") (pintype "input"))
    )
    (net (code "28") (name "Net-(U1-OUTPUT)") (class "Default")
      (node (ref "L1") (pin "2") (pinfunction "2_2") (pintype "unspecified"))
      (node (ref "U1") (pin "2") (pinfunction "OUTPUT_2") (pintype "input"))
    )
    (net (code "29") (name "Net-(U3-CFLY+)") (class "Default")
      (node (ref "C7") (pin "2") (pinfunction "2_2") (pintype "unspecified"))
      (node (ref "U3") (pin "6") (pinfunction "CFLY+_6") (pintype "unspecified"))
    )
    (net (code "30") (name "Net-(U3-CFLY-)") (class "Default")
      (node (ref "C7") (pin "1") (pinfunction "1_1") (pintype "unspecified"))
      (node (ref "U3") (pin "3") (pinfunction "CFLY-_3") (pintype "unspecified"))
    )
    (net (code "31") (name "Net-(U3-EN)") (class "Default")
      (node (ref "R3") (pin "2") (pinfunction "2_2") (pintype "input"))
      (node (ref "U3") (pin "5") (pinfunction "EN_5") (pintype "unspecified"))
    )
    (net (code "32") (name "Net-(U6-A)") (class "Default")
      (node (ref "D4") (pin "1") (pinfunction "1_1") (pintype "unspecified"))
      (node (ref "R22") (pin "2") (pinfunction "2_2") (pintype "input"))
      (node (ref "U6") (pin "6") (pinfunction "A_6") (pintype "unspecified"))
    )
    (net (code "33") (name "Net-(U6-B)") (class "Default")
      (node (ref "D4") (pin "2") (pinfunction "2_2") (pintype "unspecified"))
      (node (ref "R20") (pin "2") (pinfunction "2_2") (pintype "input"))
      (node (ref "U6") (pin "7") (pinfunction "B_7") (pintype "unspecified"))
    )
    (net (code "34") (name "Net-(U10-P3.0{slash}RxD{slash}INT4#{slash}T2CLKO)") (class "Default")
      (node (ref "H1") (pin "2") (pinfunction "2_2") (pintype "unspecified"))
      (node (ref "U10") (pin "15") (pinfunction "P3.0/RxD/INT4#/T2CLKO_15") (pintype "input"))
    )
    (net (code "35") (name "Net-(U10-P3.1{slash}TxD{slash}T2)") (class "Default")
      (node (ref "H1") (pin "1") (pinfunction "1_1") (pintype "unspecified"))
      (node (ref "U10") (pin "16") (pinfunction "P3.1/TxD/T2_16") (pintype "input"))
    )
    (net (code "36") (name "Net-(U11A-IN1-)") (class "Default")
      (node (ref "C14") (pin "1") (pinfunction "1_1") (pintype "input"))
      (node (ref "R10") (pin "1") (pinfunction "1_1") (pintype "input"))
      (node (ref "R8") (pin "1") (pinfunction "1_1") (pintype "input"))
      (node (ref "U11") (pin "2") (pinfunction "IN1-_2") (pintype "unspecified"))
    )
    (net (code "37") (name "Net-(U11A-OUT1)") (class "Default")
      (node (ref "C14") (pin "2") (pinfunction "2_2") (pintype "input"))
      (node (ref "R4") (pin "2") (pinfunction "2_2") (pintype "input"))
      (node (ref "R8") (pin "2") (pinfunction "2_2") (pintype "input"))
      (node (ref "U11") (pin "1") (pinfunction "OUT1_1") (pintype "unspecified"))
    )
    (net (code "38") (name "Net-(U11B-IN2-)") (class "Default")
      (node (ref "C16") (pin "2") (pinfunction "2_2") (pintype "input"))
      (node (ref "R10") (pin "2") (pinfunction "2_2") (pintype "input"))
      (node (ref "R10") (pin "3") (pinfunction "3_3") (pintype "input"))
      (node (ref "R11") (pin "2") (pinfunction "2_2") (pintype "input"))
      (node (ref "U11") (pin "6") (pinfunction "IN2-_6") (pintype "unspecified"))
    )
    (net (code "39") (name "Net-(U11B-OUT2)") (class "Default")
      (node (ref "C16") (pin "1") (pinfunction "1_1") (pintype "input"))
      (node (ref "R11") (pin "1") (pinfunction "1_1") (pintype "input"))
      (node (ref "R12") (pin "2") (pinfunction "2_2") (pintype "input"))
      (node (ref "U11") (pin "7") (pinfunction "OUT2_7") (pintype "unspecified"))
    )
    (net (code "40") (name "Net-(U11C-IN3+)") (class "Default")
      (node (ref "R12") (pin "1") (pinfunction "1_1") (pintype "input"))
      (node (ref "R13") (pin "2") (pinfunction "2_2") (pintype "input"))
      (node (ref "U11") (pin "10") (pinfunction "IN3+_10") (pintype "unspecified"))
    )
    (net (code "41") (name "Net-(U11C-IN3-)") (class "Default")
      (node (ref "R4") (pin "1") (pinfunction "1_1") (pintype "input"))
      (node (ref "R5") (pin "2") (pinfunction "2_2") (pintype "input"))
      (node (ref "U11") (pin "9") (pinfunction "IN3-_9") (pintype "unspecified"))
    )
    (net (code "42") (name "Net-(U11D-IN4+)") (class "Default")
      (node (ref "R6") (pin "1") (pinfunction "1_1") (pintype "input"))
      (node (ref "R7") (pin "1") (pinfunction "1_1") (pintype "input"))
      (node (ref "U11") (pin "12") (pinfunction "IN4+_12") (pintype "unspecified"))
    )
    (net (code "43") (name "P12") (class "Default")
      (node (ref "R19") (pin "1") (pinfunction "1_1") (pintype "input"))
      (node (ref "U10") (pin "5") (pinfunction "ECI/SS/ADC2/P1.2_5") (pintype "input"))
      (node (ref "U6") (pin "2") (pinfunction "#RE_2") (pintype "unspecified"))
      (node (ref "U6") (pin "3") (pinfunction "DE_3") (pintype "unspecified"))
    )
    (net (code "44") (name "P20") (class "Default")
      (node (ref "C18") (pin "2") (pinfunction "2_2") (pintype "input"))
      (node (ref "R23") (pin "2") (pinfunction "2_2") (pintype "input"))
      (node (ref "U10") (pin "23") (pinfunction "P2.0/RSTOUT_LOW_23") (pintype "input"))
      (node (ref "U7") (pin "1") (pinfunction "G_1") (pintype "unspecified"))
    )
    (net (code "45") (name "P21") (class "Default")
      (node (ref "CN5") (pin "5") (pinfunction "5_5") (pintype "unspecified"))
      (node (ref "U10") (pin "24") (pinfunction "P2.1/SCLK_2_24") (pintype "input"))
    )
    (net (code "46") (name "P22") (class "Default")
      (node (ref "CN5") (pin "4") (pinfunction "4_4") (pintype "unspecified"))
      (node (ref "U10") (pin "25") (pinfunction "P2.2/MISO_2_25") (pintype "input"))
    )
    (net (code "47") (name "P23") (class "Default")
      (node (ref "CN5") (pin "3") (pinfunction "3_3") (pintype "unspecified"))
      (node (ref "U10") (pin "26") (pinfunction "P2.3/MOSI_2_26") (pintype "input"))
    )
    (net (code "48") (name "P24") (class "Default")
      (node (ref "CN5") (pin "2") (pinfunction "2_2") (pintype "unspecified"))
      (node (ref "U10") (pin "27") (pinfunction "P2.4/ECI_3/SS_2_27") (pintype "input"))
    )
    (net (code "49") (name "P25") (class "Default")
      (node (ref "C17") (pin "2") (pinfunction "2_2") (pintype "input"))
      (node (ref "R17") (pin "2") (pinfunction "2_2") (pintype "input"))
      (node (ref "U10") (pin "28") (pinfunction "P2.5/CCP0_3_28") (pintype "input"))
      (node (ref "U5") (pin "1") (pinfunction "G_1") (pintype "unspecified"))
    )
    (net (code "50") (name "P36") (class "Default")
      (node (ref "R26") (pin "1") (pinfunction "1_1") (pintype "input"))
      (node (ref "U10") (pin "21") (pinfunction "P3.6/INT2#/RxD_2/CCP1_2_21") (pintype "input"))
    )
    (net (code "51") (name "P37") (class "Default")
      (node (ref "R15") (pin "1") (pinfunction "1_1") (pintype "input"))
      (node (ref "U10") (pin "22") (pinfunction "P3.7/INT3#/TxD_2/CCP2/CCP2_2_22") (pintype "input"))
    )
    (net (code "52") (name "SCL") (class "Default")
      (node (ref "R29") (pin "1") (pinfunction "1_1") (pintype "input"))
      (node (ref "U10") (pin "2") (pinfunction "CCP2_3/P2.7_2") (pintype "input"))
      (node (ref "U9") (pin "6") (pinfunction "SCL_6") (pintype "unspecified"))
    )
    (net (code "53") (name "SDA") (class "Default")
      (node (ref "R28") (pin "1") (pinfunction "1_1") (pintype "input"))
      (node (ref "U10") (pin "1") (pinfunction "CCP1_3/P2.6_1") (pintype "input"))
      (node (ref "U9") (pin "5") (pinfunction "SDA_5") (pintype "unspecified"))
    )
    (net (code "54") (name "SN+") (class "Default")
      (node (ref "CN4") (pin "2") (pinfunction "2_2") (pintype "unspecified"))
      (node (ref "U11") (pin "3") (pinfunction "IN1+_3") (pintype "unspecified"))
    )
    (net (code "55") (name "SN-") (class "Default")
      (node (ref "CN4") (pin "1") (pinfunction "1_1") (pintype "unspecified"))
      (node (ref "U11") (pin "5") (pinfunction "IN2+_5") (pintype "unspecified"))
    )
    (net (code "56") (name "VBAT") (class "Default")
      (node (ref "C1") (pin "1") (pinfunction "1_1") (pintype "input"))
      (node (ref "CN4") (pin "4") (pinfunction "4_4") (pintype "unspecified"))
      (node (ref "R6") (pin "2") (pinfunction "2_2") (pintype "input"))
      (node (ref "SW1") (pin "2") (pinfunction "2_2") (pintype "unspecified"))
      (node (ref "U1") (pin "1") (pinfunction "VIN_1") (pintype "input"))
    )
    (net (code "57") (name "VCC") (class "Default")
      (node (ref "C11") (pin "2") (pinfunction "2_2") (pintype "unspecified"))
      (node (ref "C12") (pin "2") (pinfunction "2_2") (pintype "input"))
      (node (ref "C15") (pin "1") (pinfunction "1_1") (pintype "input"))
      (node (ref "C17") (pin "1") (pinfunction "1_1") (pintype "input"))
      (node (ref "C18") (pin "1") (pinfunction "1_1") (pintype "input"))
      (node (ref "C2") (pin "2") (pinfunction "2_2") (pintype "input"))
      (node (ref "C20") (pin "2") (pinfunction "2_2") (pintype "input"))
      (node (ref "C21") (pin "1") (pinfunction "1_1") (pintype "input"))
      (node (ref "C23") (pin "2") (pinfunction "2_2") (pintype "input"))
      (node (ref "C3") (pin "2") (pinfunction "2_2") (pintype "input"))
      (node (ref "C4") (pin "1") (pinfunction "1_1") (pintype "input"))
      (node (ref "C5") (pin "1") (pinfunction "1_1") (pintype "unspecified"))
      (node (ref "C6") (pin "1") (pinfunction "1_1") (pintype "unspecified"))
      (node (ref "CN5") (pin "7") (pinfunction "7_7") (pintype "unspecified"))
      (node (ref "D1") (pin "1") (pinfunction "C_1") (pintype "unspecified"))
      (node (ref "H1") (pin "3") (pinfunction "3_3") (pintype "unspecified"))
      (node (ref "L1") (pin "1") (pinfunction "1_1") (pintype "unspecified"))
      (node (ref "LED1") (pin "1") (pinfunction "C_1") (pintype "input"))
      (node (ref "R17") (pin "1") (pinfunction "1_1") (pintype "input"))
      (node (ref "R18") (pin "2") (pinfunction "2_2") (pintype "input"))
      (node (ref "R21") (pin "2") (pinfunction "2_2") (pintype "input"))
      (node (ref "R23") (pin "1") (pinfunction "1_1") (pintype "input"))
      (node (ref "R28") (pin "2") (pinfunction "2_2") (pintype "input"))
      (node (ref "R29") (pin "2") (pinfunction "2_2") (pintype "input"))
      (node (ref "R3") (pin "1") (pinfunction "1_1") (pintype "input"))
      (node (ref "U1") (pin "4") (pinfunction "FEEDBACK_4") (pintype "input"))
      (node (ref "U10") (pin "12") (pinfunction "Vcc_12") (pintype "input"))
      (node (ref "U11") (pin "4") (pinfunction "VCC+_4") (pintype "unspecified"))
      (node (ref "U2") (pin "2") (pinfunction "VIN_2") (pintype "input"))
      (node (ref "U3") (pin "2") (pinfunction "IN_2") (pintype "unspecified"))
      (node (ref "U4") (pin "1") (pinfunction "1_1") (pintype "input"))
      (node (ref "U5") (pin "2") (pinfunction "S_2") (pintype "unspecified"))
      (node (ref "U6") (pin "8") (pinfunction "VCC_8") (pintype "unspecified"))
      (node (ref "U7") (pin "2") (pinfunction "S_2") (pintype "unspecified"))
      (node (ref "U8") (pin "1") (pinfunction "1_1") (pintype "input"))
      (node (ref "U9") (pin "8") (pinfunction "VCC_8") (pintype "unspecified"))
    )
    (net (code "58") (name "VEE") (class "Default")
      (node (ref "C13") (pin "2") (pinfunction "2_2") (pintype "input"))
      (node (ref "C8") (pin "2") (pinfunction "2_2") (pintype "unspecified"))
      (node (ref "U11") (pin "11") (pinfunction "VCC-_11") (pintype "unspecified"))
      (node (ref "U3") (pin "1") (pinfunction "OUT_1") (pintype "unspecified"))
    )
    (net (code "59") (name "VRM") (class "Default")
      (node (ref "C10") (pin "2") (pinfunction "2_2") (pintype "input"))
      (node (ref "C9") (pin "2") (pinfunction "2_2") (pintype "unspecified"))
      (node (ref "D3") (pin "1") (pinfunction "C_1") (pintype "unspecified"))
      (node (ref "D5") (pin "1") (pinfunction "C_1") (pintype "unspecified"))
      (node (ref "R14") (pin "1") (pinfunction "1_1") (pintype "input"))
      (node (ref "R2") (pin "2") (pinfunction "2_2") (pintype "input"))
      (node (ref "R24") (pin "2") (pinfunction "2_2") (pintype "input"))
      (node (ref "R25") (pin "1") (pinfunction "1_1") (pintype "input"))
      (node (ref "R9") (pin "2") (pinfunction "2_2") (pintype "input"))
      (node (ref "RELAY1") (pin "2") (pinfunction "2_2") (pintype "input"))
      (node (ref "RELAY2") (pin "2") (pinfunction "2_2") (pintype "input"))
      (node (ref "U2") (pin "4") (pinfunction "+Vo_4") (pintype "input"))
    )
    (net (code "60") (name "XTAL1") (class "Default")
      (node (ref "C19") (pin "1") (pinfunction "1_1") (pintype "input"))
      (node (ref "U10") (pin "10") (pinfunction "XTAL1/TxD_3/ADC7/P1.7_10") (pintype "input"))
      (node (ref "X1") (pin "2") (pinfunction "2_2") (pintype "unspecified"))
    )
    (net (code "61") (name "XTAL2") (class "Default")
      (node (ref "C22") (pin "1") (pinfunction "1_1") (pintype "input"))
      (node (ref "U10") (pin "9") (pinfunction "XTAL2/RxD_3/ADC6/P1.6_9") (pintype "input"))
      (node (ref "X1") (pin "1") (pinfunction "1_1") (pintype "unspecified"))
    )
    (net (code "62") (name "unconnected-(SW1-Pad3)") (class "Default")
      (node (ref "SW1") (pin "3") (pinfunction "3_3") (pintype "unspecified+no_connect"))
    )
    (net (code "63") (name "unconnected-(SW1-Pad4)") (class "Default")
      (node (ref "SW1") (pin "4") (pinfunction "4_4") (pintype "unspecified+no_connect"))
    )
    (net (code "64") (name "unconnected-(SW1-Pad5)") (class "Default")
      (node (ref "SW1") (pin "5") (pinfunction "5_5") (pintype "unspecified+no_connect"))
    )
    (net (code "65") (name "unconnected-(U10-MCLKO{slash}RST{slash}P5.4-Pad11)") (class "Default")
      (node (ref "U10") (pin "11") (pinfunction "MCLKO/RST/P5.4_11") (pintype "input+no_connect"))
    )
    (net (code "66") (name "unconnected-(U10-P3.2{slash}INT0-Pad17)") (class "Default")
      (node (ref "U10") (pin "17") (pinfunction "P3.2/INT0_17") (pintype "input+no_connect"))
    )
    (net (code "67") (name "unconnected-(U10-P3.3{slash}INT1-Pad18)") (class "Default")
      (node (ref "U10") (pin "18") (pinfunction "P3.3/INT1_18") (pintype "input+no_connect"))
    )
    (net (code "68") (name "unconnected-(U10-P3.4{slash}T0{slash}T1CLKO{slash}ECI_2-Pad19)") (class "Default")
      (node (ref "U10") (pin "19") (pinfunction "P3.4/T0/T1CLKO/ECI_2_19") (pintype "input+no_connect"))
    )
    (net (code "69") (name "unconnected-(U10-P3.5{slash}T1{slash}T0CLKO{slash}CCP0_2-Pad20)") (class "Default")
      (node (ref "U10") (pin "20") (pinfunction "P3.5/T1/T0CLKO/CCP0_2_20") (pintype "input+no_connect"))
    )
    (net (code "70") (name "unconnected-(U10-P5.5-Pad13)") (class "Default")
      (node (ref "U10") (pin "13") (pinfunction "P5.5_13") (pintype "input+no_connect"))
    )
    (net (code "71") (name "unconnected-(U10-SCLK{slash}ADC5{slash}P1.5-Pad8)") (class "Default")
      (node (ref "U10") (pin "8") (pinfunction "SCLK/ADC5/P1.5_8") (pintype "input+no_connect"))
    )
  )
)
